# Sheet1.net
KiCad netlist of a schematic drawn in Altium Designer
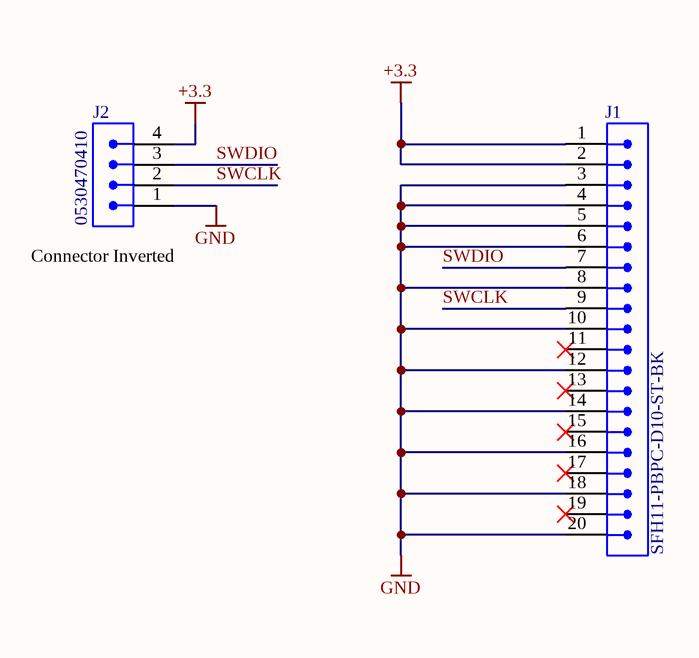
[diagram p0: Sheet1.SchDoc]

(export (version "E")
  (design (tool "Eeschema 10.0.6"))
  (components
    (comp (ref "J1")
      (value "SFH11-PBPC-D10-ST-BK")
      (footprint "2x10")
      (description "20 Position Header Connector 0.100\" (2.54mm) Through Hole Gold")
      (libsource (lib "Sullins Connector Solutions") (part "SFH11-PBPC-D10-ST-BK"))
    )
    (comp (ref "J2")
      (value "0530470410")
      (footprint "4POS")
      (description "Connector Header Through Hole 4 position 0.049\" (1.25mm)")
      (libsource (lib "Molex") (part "0530470410"))
    )
  )
  (nets
    (net (code "1") (name "+3.3") (class "Default")
      (node (ref "J1") (pin "1") (pinfunction "1_1") (pintype "passive"))
      (node (ref "J1") (pin "2") (pinfunction "2_2") (pintype "passive"))
      (node (ref "J2") (pin "4") (pinfunction "4_4") (pintype "passive"))
    )
    (net (code "2") (name "/SWCLK") (class "Default")
      (node (ref "J1") (pin "9") (pinfunction "9_9") (pintype "passive"))
      (node (ref "J2") (pin "2") (pinfunction "2_2") (pintype "passive"))
    )
    (net (code "3") (name "/SWDIO") (class "Default")
      (node (ref "J1") (pin "7") (pinfunction "7_7") (pintype "passive"))
      (node (ref "J2") (pin "3") (pinfunction "3_3") (pintype "passive"))
    )
    (net (code "4") (name "GND") (class "Default")
      (node (ref "J1") (pin "10") (pinfunction "10_10") (pintype "passive"))
      (node (ref "J1") (pin "12") (pinfunction "12_12") (pintype "passive"))
      (node (ref "J1") (pin "14") (pinfunction "14_14") (pintype "passive"))
      (node (ref "J1") (pin "16") (pinfunction "16_16") (pintype "passive"))
      (node (ref "J1") (pin "18") (pinfunction "18_18") (pintype "passive"))
      (node (ref "J1") (pin "20") (pinfunction "20_20") (pintype "passive"))
      (node (ref "J1") (pin "3") (pinfunction "3_3") (pintype "passive"))
      (node (ref "J1") (pin "4") (pinfunction "4_4") (pintype "passive"))
      (node (ref "J1") (pin "5") (pinfunction "5_5") (pintype "passive"))
      (node (ref "J1") (pin "6") (pinfunction "6_6") (pintype "passive"))
      (node (ref "J1") (pin "8") (pinfunction "8_8") (pintype "passive"))
      (node (ref "J2") (pin "1") (pinfunction "1_1") (pintype "passive"))
    )
    (net (code "5") (name "unconnected-(J1-Pad11)") (class "Default")
      (node (ref "J1") (pin "11") (pinfunction "11_11") (pintype "passive+no_connect"))
    )
    (net (code "6") (name "unconnected-(J1-Pad13)") (class "Default")
      (node (ref "J1") (pin "13") (pinfunction "13_13") (pintype "passive+no_connect"))
    )
    (net (code "7") (name "unconnected-(J1-Pad15)") (class "Default")
      (node (ref "J1") (pin "15") (pinfunction "15_15") (pintype "passive+no_connect"))
    )
    (net (code "8") (name "unconnected-(J1-Pad17)") (class "Default")
      (node (ref "J1") (pin "17") (pinfunction "17_17") (pintype "passive+no_connect"))
    )
    (net (code "9") (name "unconnected-(J1-Pad19)") (class "Default")
      (node (ref "J1") (pin "19") (pinfunction "19_19") (pintype "passive+no_connect"))
    )
  )
)
